# Modular_E-Fuse_rev1.net
KiCad netlist of a schematic drawn in EAGLE
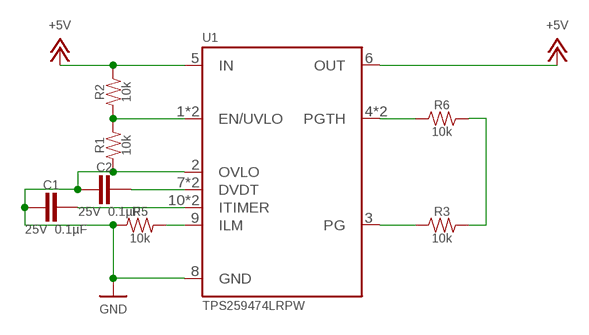
[diagram p0: schematic, sheet 1]

(export (version "E")
  (design (tool "Eeschema 10.0.6"))
  (components
    (comp (ref "C1")
      (value "CAPACITOR_0603_25V_0.1UF")
      (footprint "eagle-import:0603-CAP")
      (fields
        (field (name "CAPACITANCE") "0.1µF")
        (field (name "MANUFACTURER") "Samsung Electro-Mechanics")
        (field (name "MPN") "CL10B104KA8NNNC")
        (field (name "TOLERANCE") "10%")
        (field (name "VOLTAGE") "25V")
      )
      (libsource (lib "eagle-import") (part "CAPACITOR_?_060325V_0.1UF"))
    )
    (comp (ref "C2")
      (value "CAPACITOR_0603_25V_0.1UF")
      (footprint "eagle-import:0603-CAP")
      (fields
        (field (name "CAPACITANCE") "0.1µF")
        (field (name "MANUFACTURER") "Samsung Electro-Mechanics")
        (field (name "MPN") "CL10B104KA8NNNC")
        (field (name "TOLERANCE") "10%")
        (field (name "VOLTAGE") "25V")
      )
      (libsource (lib "eagle-import") (part "CAPACITOR_?_060325V_0.1UF"))
    )
    (comp (ref "R1")
      (value "RESISTOR_0603_10K")
      (footprint "eagle-import:0603-RES")
      (fields
        (field (name "MANUFACTURER") "Yageo")
        (field (name "MPN") "RC0603FR-0710KL")
        (field (name "POWER") "0.1W")
        (field (name "RESISTANCE") "10k")
      )
      (libsource (lib "eagle-import") (part "RESISTOR_?_060310K"))
    )
    (comp (ref "R2")
      (value "RESISTOR_0603_10K")
      (footprint "eagle-import:0603-RES")
      (fields
        (field (name "MANUFACTURER") "Yageo")
        (field (name "MPN") "RC0603FR-0710KL")
        (field (name "POWER") "0.1W")
        (field (name "RESISTANCE") "10k")
      )
      (libsource (lib "eagle-import") (part "RESISTOR_?_060310K"))
    )
    (comp (ref "R3")
      (value "RESISTOR_0603_10K")
      (footprint "eagle-import:0603-RES")
      (fields
        (field (name "MANUFACTURER") "Yageo")
        (field (name "MPN") "RC0603FR-0710KL")
        (field (name "POWER") "0.1W")
        (field (name "RESISTANCE") "10k")
      )
      (libsource (lib "eagle-import") (part "RESISTOR_?_060310K"))
    )
    (comp (ref "R5")
      (value "RESISTOR_0603_10K")
      (footprint "eagle-import:0603-RES")
      (fields
        (field (name "MANUFACTURER") "Yageo")
        (field (name "MPN") "RC0603FR-0710KL")
        (field (name "POWER") "0.1W")
        (field (name "RESISTANCE") "10k")
      )
      (libsource (lib "eagle-import") (part "RESISTOR_?_060310K"))
    )
    (comp (ref "R6")
      (value "RESISTOR_0603_10K")
      (footprint "eagle-import:0603-RES")
      (fields
        (field (name "MANUFACTURER") "Yageo")
        (field (name "MPN") "RC0603FR-0710KL")
        (field (name "POWER") "0.1W")
        (field (name "RESISTANCE") "10k")
      )
      (libsource (lib "eagle-import") (part "RESISTOR_?_060310K"))
    )
    (comp (ref "U1")
      (value "TPS259474LRPW")
      (footprint "eagle-import:VQFN-HR-10")
      (fields (field (name "MPN") "TPS259474LRPW"))
      (libsource (lib "eagle-import") (part "TPS259474LRPW"))
    )
  )
  (nets
    (net (code "1") (name "+5V") (class "Default")
      (node (ref "R2") (pin "2") (pinfunction "2_2") (pintype "passive"))
      (node (ref "U1") (pin "5") (pinfunction "IN_5") (pintype "input"))
      (node (ref "U1") (pin "6") (pinfunction "OUT_6") (pintype "output"))
    )
    (net (code "2") (name "GND") (class "Default")
      (node (ref "C1") (pin "2") (pinfunction "2_2") (pintype "passive"))
      (node (ref "C2") (pin "2") (pinfunction "2_2") (pintype "passive"))
      (node (ref "R1") (pin "1") (pinfunction "1_1") (pintype "passive"))
      (node (ref "R5") (pin "1") (pinfunction "1_1") (pintype "passive"))
      (node (ref "U1") (pin "2") (pinfunction "OVLO_2") (pintype "input"))
      (node (ref "U1") (pin "8") (pinfunction "GND_8") (pintype "power_in"))
    )
    (net (code "3") (name "Net-(C1-Pad1)") (class "Default")
      (node (ref "C1") (pin "1") (pinfunction "1_1") (pintype "passive"))
      (node (ref "U1") (pin "10") (pinfunction "ITIMER_10") (pintype "output"))
      (node (ref "U1") (pin "10@2") (pinfunction "ITIMER_10@2") (pintype "output"))
    )
    (net (code "4") (name "Net-(C2-Pad1)") (class "Default")
      (node (ref "C2") (pin "1") (pinfunction "1_1") (pintype "passive"))
      (node (ref "U1") (pin "7") (pinfunction "DVDT_7") (pintype "output"))
      (node (ref "U1") (pin "7@2") (pinfunction "DVDT_7@2") (pintype "output"))
    )
    (net (code "5") (name "Net-(R1-Pad2)") (class "Default")
      (node (ref "R1") (pin "2") (pinfunction "2_2") (pintype "passive"))
      (node (ref "R2") (pin "1") (pinfunction "1_1") (pintype "passive"))
      (node (ref "U1") (pin "1") (pinfunction "EN/UVLO_1") (pintype "input"))
      (node (ref "U1") (pin "1@2") (pinfunction "EN/UVLO_1@2") (pintype "input"))
    )
    (net (code "6") (name "Net-(R3-Pad2)") (class "Default")
      (node (ref "R3") (pin "2") (pinfunction "2_2") (pintype "passive"))
      (node (ref "R6") (pin "2") (pinfunction "2_2") (pintype "passive"))
    )
    (net (code "7") (name "Net-(R6-Pad1)") (class "Default")
      (node (ref "R6") (pin "1") (pinfunction "1_1") (pintype "passive"))
      (node (ref "U1") (pin "4") (pinfunction "PGTH_4") (pintype "input"))
      (node (ref "U1") (pin "4@2") (pinfunction "PGTH_4@2") (pintype "input"))
    )
    (net (code "8") (name "Net-(U1-ILM)") (class "Default")
      (node (ref "R5") (pin "2") (pinfunction "2_2") (pintype "passive"))
      (node (ref "U1") (pin "9") (pinfunction "ILM_9") (pintype "output"))
    )
    (net (code "9") (name "Net-(U1-PG)") (class "Default")
      (node (ref "R3") (pin "1") (pinfunction "1_1") (pintype "passive"))
      (node (ref "U1") (pin "3") (pinfunction "PG_3") (pintype "open_collector"))
    )
  )
)
